# Servo_2016.net
KiCad netlist of a schematic drawn in EAGLE
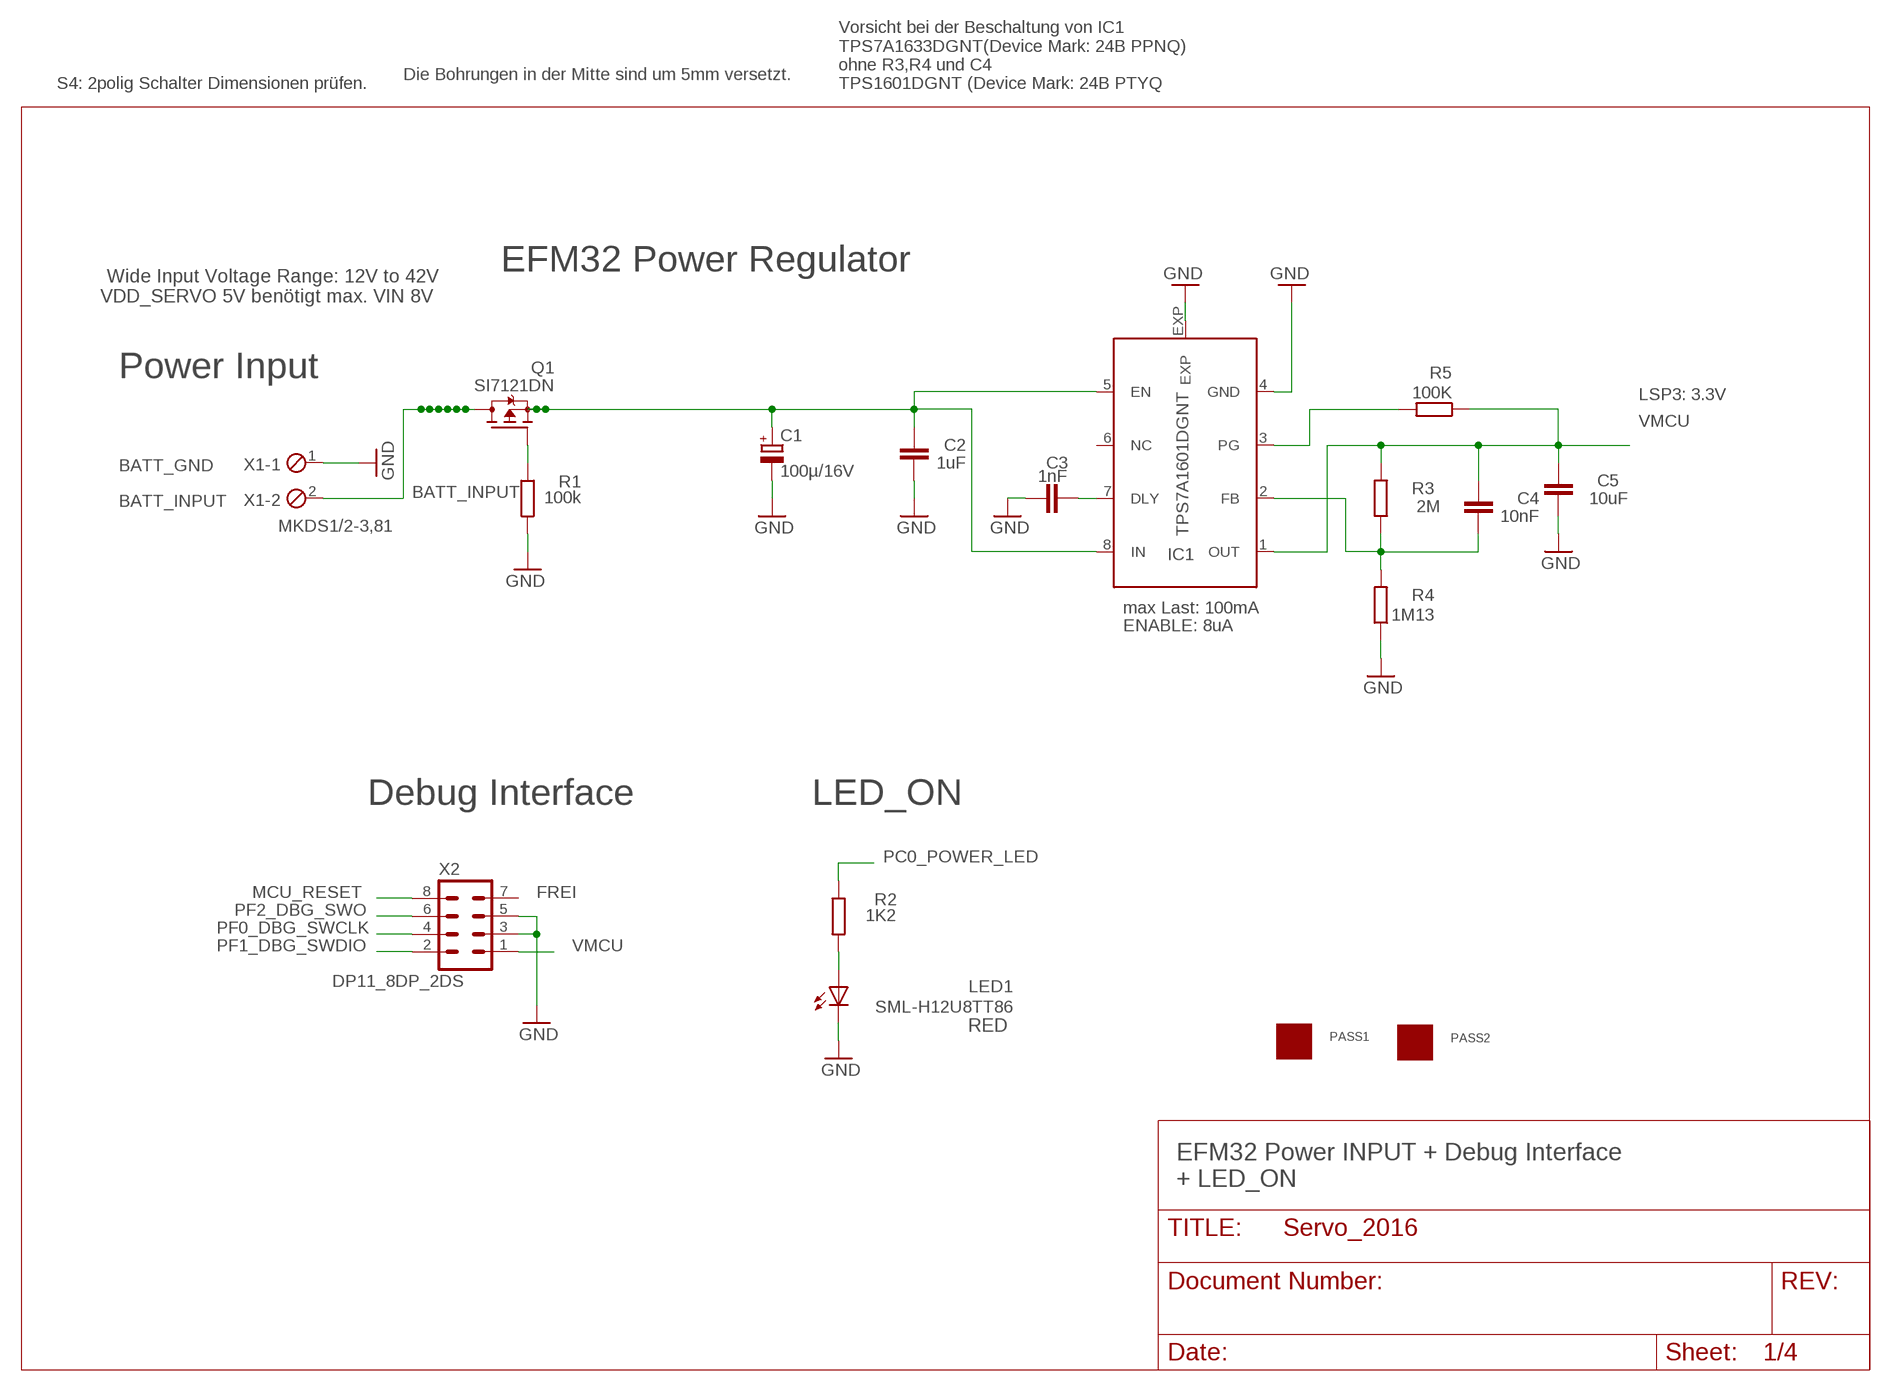
[diagram p0: schematic, sheet 1]
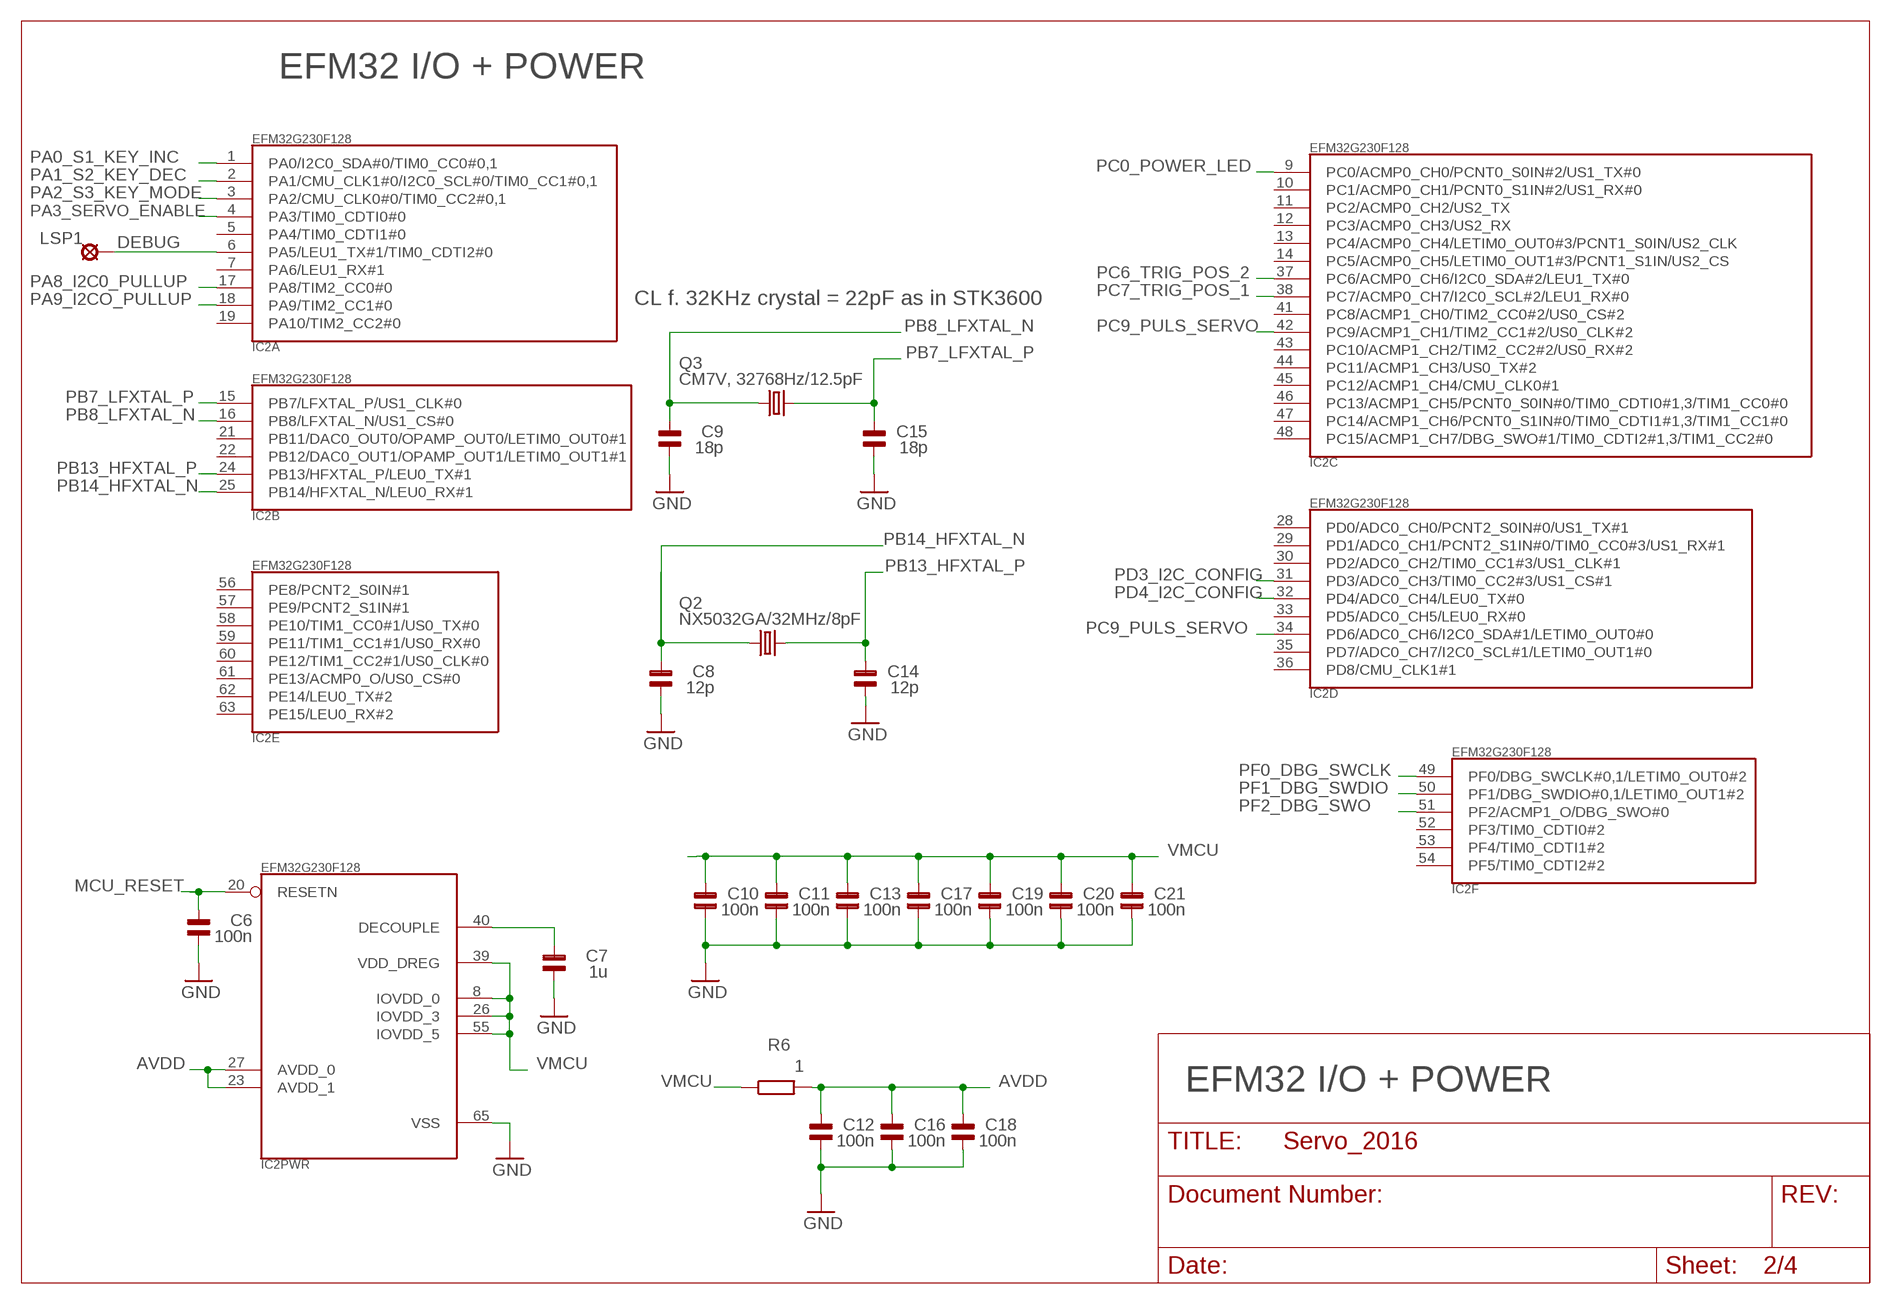
[diagram p1: schematic, sheet 2]
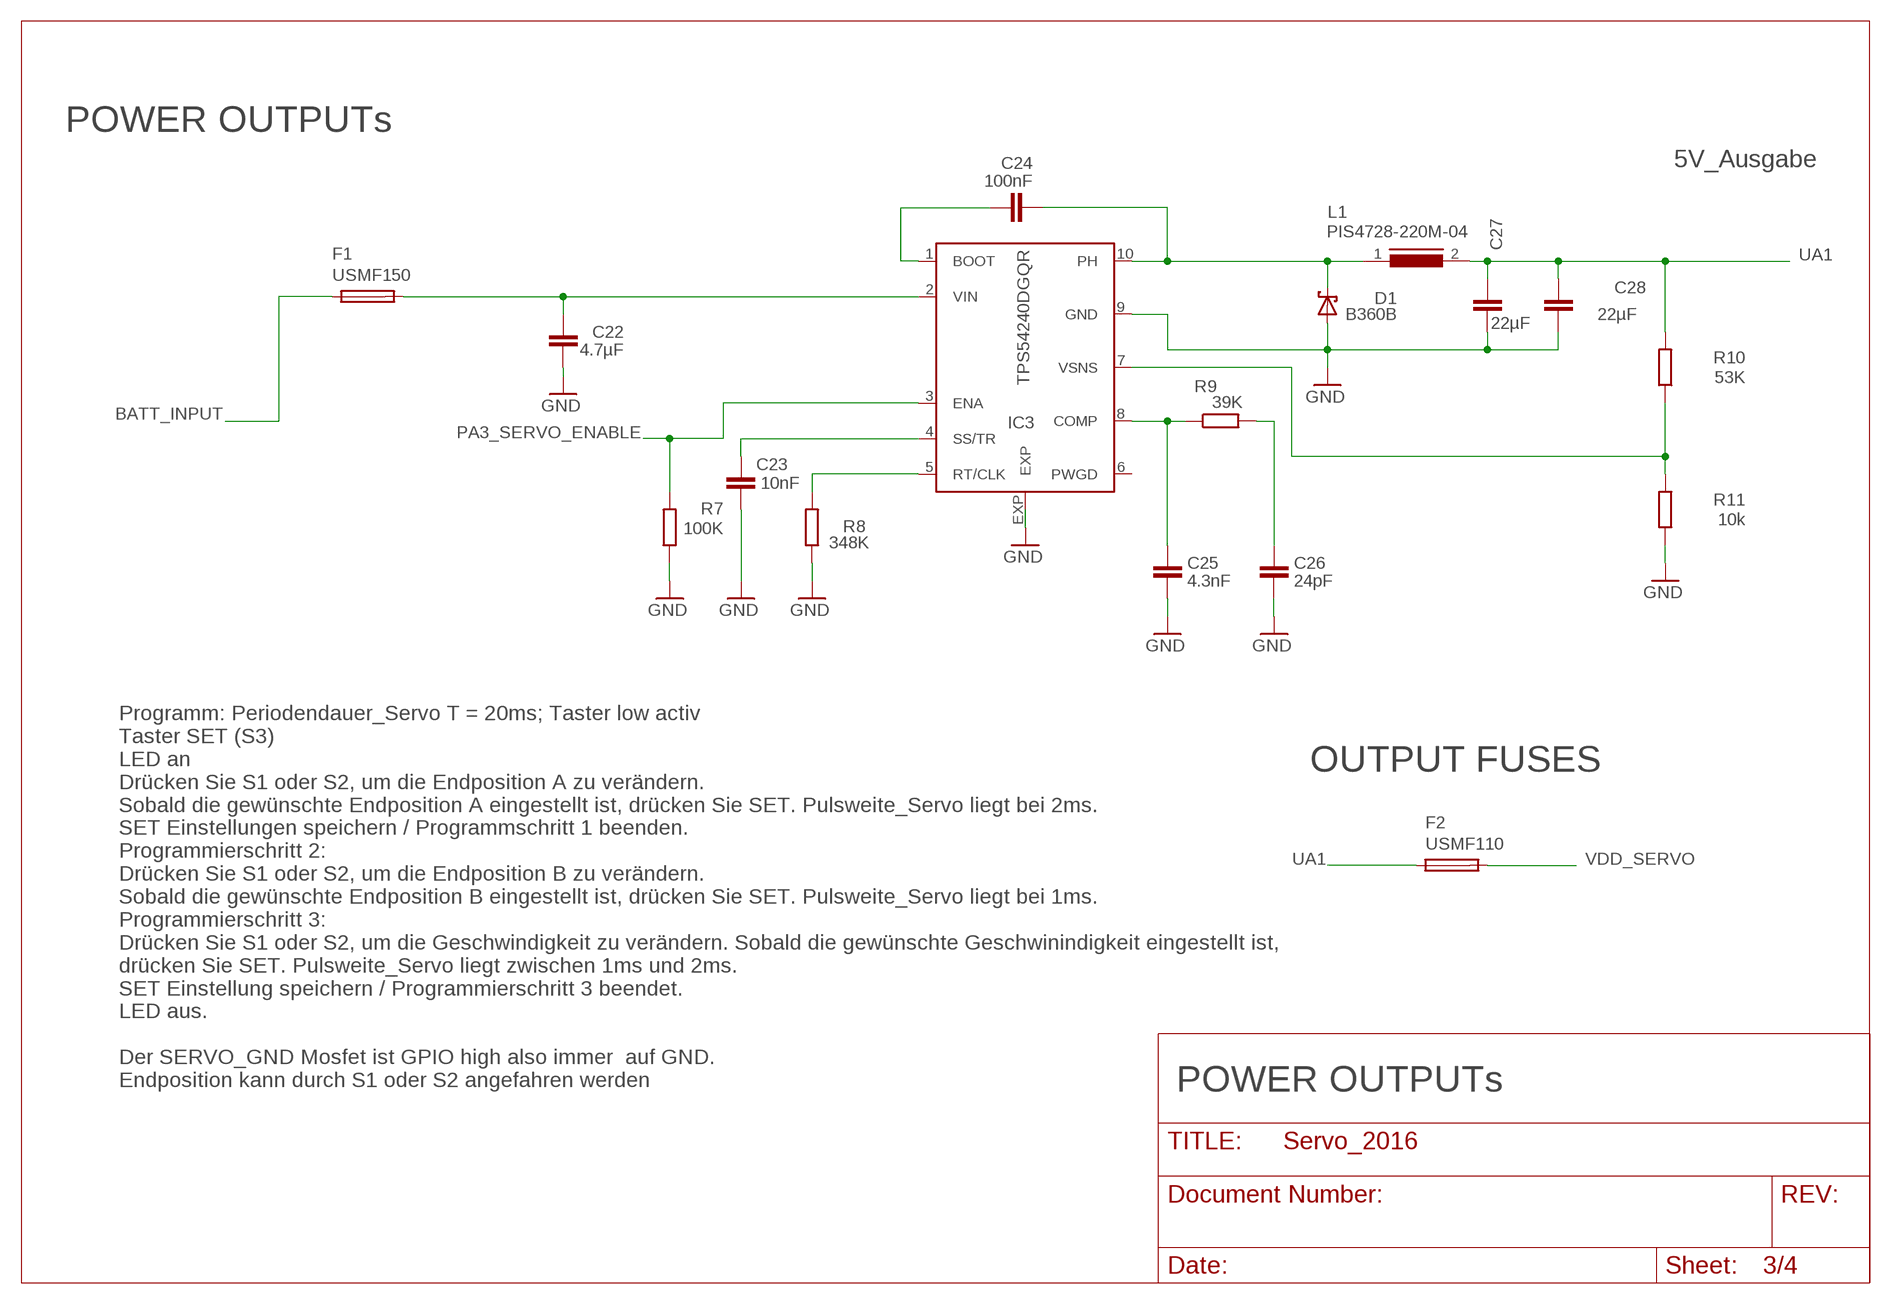
[diagram p2: schematic, sheet 3]
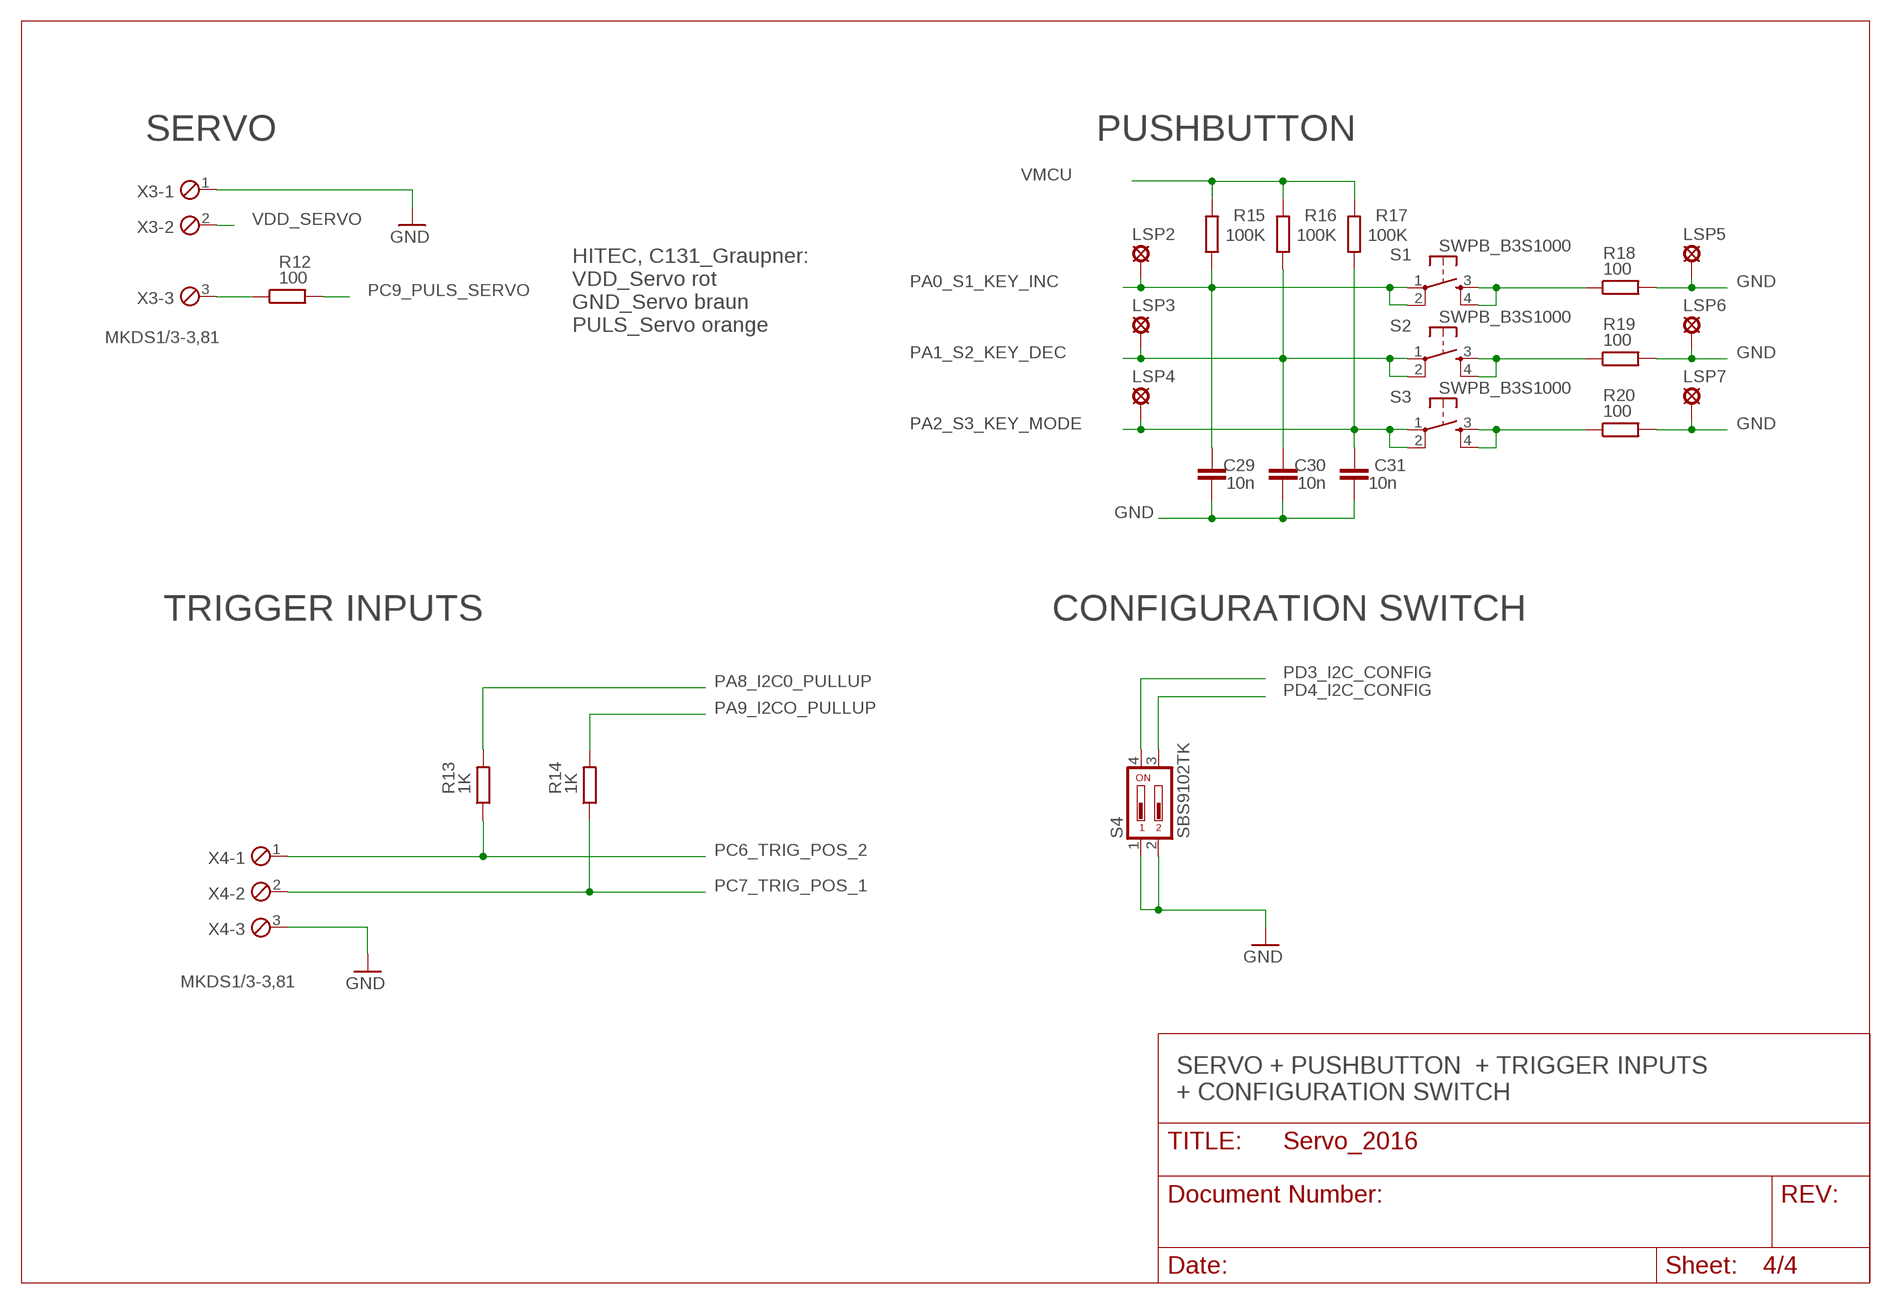
[diagram p3: schematic, sheet 4]

(export (version "E")
  (design (tool "Eeschema 10.0.6"))
  (components
    (comp (ref "C22")
      (value "4.7µF")
      (footprint "eagle-import:C1210")
      (libsource (lib "eagle-import") (part "C-EUC1210"))
    )
    (comp (ref "C23")
      (value "10nF")
      (footprint "eagle-import:C0603")
      (libsource (lib "eagle-import") (part "C-EUC0603"))
    )
    (comp (ref "C24")
      (value "100nF")
      (footprint "eagle-import:C0603")
      (libsource (lib "eagle-import") (part "C-EUC0603"))
    )
    (comp (ref "C25")
      (value "4.3nF")
      (footprint "eagle-import:C0603")
      (libsource (lib "eagle-import") (part "C-EUC0603"))
    )
    (comp (ref "C26")
      (value "24pF")
      (footprint "eagle-import:C0603")
      (libsource (lib "eagle-import") (part "C-EUC0603"))
    )
    (comp (ref "C27")
      (value "22µF")
      (footprint "eagle-import:C1210")
      (libsource (lib "eagle-import") (part "C-EUC1210"))
    )
    (comp (ref "C28")
      (value "22µF")
      (footprint "eagle-import:C1210")
      (libsource (lib "eagle-import") (part "C-EUC1210"))
    )
    (comp (ref "D1")
      (value "B360B")
      (footprint "eagle-import:SMB")
      (libsource (lib "eagle-import") (part "SCHOTTKY-DIODESMD"))
    )
    (comp (ref "F1")
      (value "USMF150")
      (footprint "eagle-import:PFUF_1210POLY")
      (libsource (lib "eagle-import") (part "PFUF"))
    )
    (comp (ref "F2")
      (value "USMF110")
      (footprint "eagle-import:PFUF_1210POLY")
      (libsource (lib "eagle-import") (part "PFUF"))
    )
    (comp (ref "IC3")
      (value "TPS54240DGQR")
      (footprint "eagle-import:S-PDSO-G10")
      (libsource (lib "eagle-import") (part "TPS54240DGQR"))
    )
    (comp (ref "L1")
      (value "PIS4728-220M-04")
      (footprint "eagle-import:DR127")
      (libsource (lib "eagle-import") (part "DR127"))
    )
    (comp (ref "R7")
      (value "100K")
      (footprint "eagle-import:R0805")
      (libsource (lib "eagle-import") (part "resistor_R-EU_R0805"))
    )
    (comp (ref "R8")
      (value "348K")
      (footprint "eagle-import:R0805")
      (libsource (lib "eagle-import") (part "resistor_R-EU_R0805"))
    )
    (comp (ref "R9")
      (value "39K")
      (footprint "eagle-import:R0805")
      (libsource (lib "eagle-import") (part "resistor_R-EU_R0805"))
    )
    (comp (ref "R10")
      (value "53K")
      (footprint "eagle-import:R0805")
      (libsource (lib "eagle-import") (part "resistor_R-EU_R0805"))
    )
    (comp (ref "R11")
      (value "10k")
      (footprint "eagle-import:R0805")
      (libsource (lib "eagle-import") (part "resistor_R-EU_R0805"))
    )
    (comp (ref "C1")
      (value "100µ/16V")
      (footprint "eagle-import:PANASONIC_E")
      (libsource (lib "eagle-import") (part "CPOL-EUE"))
    )
    (comp (ref "C2")
      (value "1uF")
      (footprint "eagle-import:C0603")
      (libsource (lib "eagle-import") (part "resistor_C-EUC0603"))
    )
    (comp (ref "C3")
      (value "1nF")
      (footprint "eagle-import:C0603")
      (libsource (lib "eagle-import") (part "resistor_C-EUC0603"))
    )
    (comp (ref "C4")
      (value "10nF")
      (footprint "eagle-import:C0603")
      (libsource (lib "eagle-import") (part "resistor_C-EUC0603"))
    )
    (comp (ref "C5")
      (value "10uF")
      (footprint "eagle-import:C1206")
      (libsource (lib "eagle-import") (part "resistor_C-EUC1206"))
    )
    (comp (ref "IC1")
      (value "TPS7A1601DGNT")
      (footprint "eagle-import:DGN_S-PDSO-G8-EXP")
      (libsource (lib "eagle-import") (part "TPS7A16"))
    )
    (comp (ref "LED1")
      (value "SML-H12U8TT86")
      (footprint "eagle-import:CHIPLED_0805")
      (libsource (lib "eagle-import") (part "LEDCHIPLED_0805"))
    )
    (comp (ref "PASS1")
      (value "ROUND_1MM1.5")
      (footprint "eagle-import:ROUND2_1.5MM")
      (libsource (lib "eagle-import") (part "ROUND_1MM1.5"))
    )
    (comp (ref "PASS2")
      (value "ROUND_1MM1.5")
      (footprint "eagle-import:ROUND2_1.5MM")
      (libsource (lib "eagle-import") (part "ROUND_1MM1.5"))
    )
    (comp (ref "Q1")
      (value "SI7121DN")
      (footprint "eagle-import:TRANSISTOR-FET_1212-8S")
      (libsource (lib "eagle-import") (part "TRANSISTOR-FET_SI7113DN"))
    )
    (comp (ref "R1")
      (value "100k")
      (footprint "eagle-import:R0805")
      (libsource (lib "eagle-import") (part "resistor_R-EU_R0805"))
    )
    (comp (ref "R2")
      (value "1K2")
      (footprint "eagle-import:R0805")
      (libsource (lib "eagle-import") (part "resistor_R-EU_R0805"))
    )
    (comp (ref "R3")
      (value "2M")
      (footprint "eagle-import:R0805")
      (libsource (lib "eagle-import") (part "resistor_R-EU_R0805"))
    )
    (comp (ref "R4")
      (value "1M13")
      (footprint "eagle-import:R0805")
      (libsource (lib "eagle-import") (part "resistor_R-EU_R0805"))
    )
    (comp (ref "R5")
      (value "100K")
      (footprint "eagle-import:R0805")
      (libsource (lib "eagle-import") (part "resistor_R-EU_R0805"))
    )
    (comp (ref "X1")
      (value "MKDS1/2-3,81")
      (footprint "eagle-import:2POL381")
      (libsource (lib "eagle-import") (part "MKDS1/2-3,81"))
    )
    (comp (ref "X2")
      (value "DP11_8DP_2DS")
      (footprint "eagle-import:DP11_8DP-2DS")
      (libsource (lib "eagle-import") (part "DP11_8DP_2DS"))
    )
    (comp (ref "C29")
      (value "10n")
      (footprint "eagle-import:C0603")
      (libsource (lib "eagle-import") (part "resistor_C-EUC0603"))
    )
    (comp (ref "C30")
      (value "10n")
      (footprint "eagle-import:C0603")
      (libsource (lib "eagle-import") (part "resistor_C-EUC0603"))
    )
    (comp (ref "C31")
      (value "10n")
      (footprint "eagle-import:C0603")
      (libsource (lib "eagle-import") (part "resistor_C-EUC0603"))
    )
    (comp (ref "LSP2")
      (value "(n.b.)LSP10")
      (footprint "eagle-import:LSP10")
      (libsource (lib "eagle-import") (part "LSP10"))
    )
    (comp (ref "LSP3")
      (value "(n.b.)LSP10")
      (footprint "eagle-import:LSP10")
      (libsource (lib "eagle-import") (part "LSP10"))
    )
    (comp (ref "LSP4")
      (value "(n.b.)LSP10")
      (footprint "eagle-import:LSP10")
      (libsource (lib "eagle-import") (part "LSP10"))
    )
    (comp (ref "LSP5")
      (value "(n.b.)LSP10")
      (footprint "eagle-import:LSP10")
      (libsource (lib "eagle-import") (part "LSP10"))
    )
    (comp (ref "LSP6")
      (value "(n.b.)LSP10")
      (footprint "eagle-import:LSP10")
      (libsource (lib "eagle-import") (part "LSP10"))
    )
    (comp (ref "LSP7")
      (value "(n.b.)LSP10")
      (footprint "eagle-import:LSP10")
      (libsource (lib "eagle-import") (part "LSP10"))
    )
    (comp (ref "R12")
      (value "100")
      (footprint "eagle-import:R0805")
      (libsource (lib "eagle-import") (part "resistor_R-EU_R0805"))
    )
    (comp (ref "R13")
      (value "1K")
      (footprint "eagle-import:R0805")
      (libsource (lib "eagle-import") (part "resistor_R-EU_R0805"))
    )
    (comp (ref "R14")
      (value "1K")
      (footprint "eagle-import:R0805")
      (libsource (lib "eagle-import") (part "resistor_R-EU_R0805"))
    )
    (comp (ref "R15")
      (value "100K")
      (footprint "eagle-import:R0805")
      (libsource (lib "eagle-import") (part "resistor_R-EU_R0805"))
    )
    (comp (ref "R16")
      (value "100K")
      (footprint "eagle-import:R0805")
      (libsource (lib "eagle-import") (part "resistor_R-EU_R0805"))
    )
    (comp (ref "R17")
      (value "100K")
      (footprint "eagle-import:R0805")
      (libsource (lib "eagle-import") (part "resistor_R-EU_R0805"))
    )
    (comp (ref "R18")
      (value "100")
      (footprint "eagle-import:R0805")
      (libsource (lib "eagle-import") (part "resistor_R-EU_R0805"))
    )
    (comp (ref "R19")
      (value "100")
      (footprint "eagle-import:R0805")
      (libsource (lib "eagle-import") (part "resistor_R-EU_R0805"))
    )
    (comp (ref "R20")
      (value "100")
      (footprint "eagle-import:R0805")
      (libsource (lib "eagle-import") (part "resistor_R-EU_R0805"))
    )
    (comp (ref "S1")
      (value "SWPB_B3S1000")
      (footprint "eagle-import:DTSM-6")
      (libsource (lib "eagle-import") (part "DTSM-6"))
    )
    (comp (ref "S2")
      (value "SWPB_B3S1000")
      (footprint "eagle-import:DTSM-6")
      (libsource (lib "eagle-import") (part "DTSM-6"))
    )
    (comp (ref "S3")
      (value "SWPB_B3S1000")
      (footprint "eagle-import:DTSM-6")
      (libsource (lib "eagle-import") (part "DTSM-6"))
    )
    (comp (ref "S4")
      (value "SBS9102TK")
      (footprint "eagle-import:CTS-219-02")
      (libsource (lib "eagle-import") (part "219-02"))
    )
    (comp (ref "X3")
      (value "MKDS1/3-3,81")
      (footprint "eagle-import:3POL381")
      (libsource (lib "eagle-import") (part "MKDS1/3-3,81"))
    )
    (comp (ref "X4")
      (value "MKDS1/3-3,81")
      (footprint "eagle-import:3POL381")
      (libsource (lib "eagle-import") (part "MKDS1/3-3,81"))
    )
    (comp (ref "C6")
      (value "100n")
      (footprint "eagle-import:0805")
      (libsource (lib "eagle-import") (part "C_SMD0805"))
    )
    (comp (ref "C7")
      (value "1u")
      (footprint "eagle-import:0805")
      (libsource (lib "eagle-import") (part "C_SMD0805"))
    )
    (comp (ref "C8")
      (value "12p")
      (footprint "eagle-import:0805")
      (libsource (lib "eagle-import") (part "C_SMD0805"))
    )
    (comp (ref "C9")
      (value "18p")
      (footprint "eagle-import:0805")
      (libsource (lib "eagle-import") (part "C_SMD0805"))
    )
    (comp (ref "C10")
      (value "100n")
      (footprint "eagle-import:0805")
      (libsource (lib "eagle-import") (part "C_SMD0805"))
    )
    (comp (ref "C11")
      (value "100n")
      (footprint "eagle-import:0805")
      (libsource (lib "eagle-import") (part "C_SMD0805"))
    )
    (comp (ref "C12")
      (value "100n")
      (footprint "eagle-import:0805")
      (libsource (lib "eagle-import") (part "C_SMD0805"))
    )
    (comp (ref "C13")
      (value "100n")
      (footprint "eagle-import:0805")
      (libsource (lib "eagle-import") (part "C_SMD0805"))
    )
    (comp (ref "C14")
      (value "12p")
      (footprint "eagle-import:0805")
      (libsource (lib "eagle-import") (part "C_SMD0805"))
    )
    (comp (ref "C15")
      (value "18p")
      (footprint "eagle-import:0805")
      (libsource (lib "eagle-import") (part "C_SMD0805"))
    )
    (comp (ref "C16")
      (value "100n")
      (footprint "eagle-import:0805")
      (libsource (lib "eagle-import") (part "C_SMD0805"))
    )
    (comp (ref "C17")
      (value "100n")
      (footprint "eagle-import:0805")
      (libsource (lib "eagle-import") (part "C_SMD0805"))
    )
    (comp (ref "C18")
      (value "100n")
      (footprint "eagle-import:0805")
      (libsource (lib "eagle-import") (part "C_SMD0805"))
    )
    (comp (ref "C19")
      (value "100n")
      (footprint "eagle-import:0805")
      (libsource (lib "eagle-import") (part "C_SMD0805"))
    )
    (comp (ref "C20")
      (value "100n")
      (footprint "eagle-import:0805")
      (libsource (lib "eagle-import") (part "C_SMD0805"))
    )
    (comp (ref "C21")
      (value "100n")
      (footprint "eagle-import:0805")
      (libsource (lib "eagle-import") (part "C_SMD0805"))
    )
    (comp (ref "IC2")
      (value "EFM32G230F128")
      (footprint "eagle-import:QFN64")
      (libsource (lib "eagle-import") (part "EFM32G230F128"))
    )
    (comp (ref "LSP1")
      (value "(n.b.)LSP10")
      (footprint "eagle-import:LSP10")
      (libsource (lib "eagle-import") (part "LSP10"))
    )
    (comp (ref "Q2")
      (value "NX5032GA/32MHz/8pF")
      (footprint "eagle-import:CRYSTAL2P5.0X3.2")
      (libsource (lib "eagle-import") (part "CRYSTAL2P5.0X3.2"))
    )
    (comp (ref "Q3")
      (value "CM7V, 32768Hz/12.5pF")
      (footprint "eagle-import:CRYSTAL2P3.2X1.5")
      (libsource (lib "eagle-import") (part "CRYSTAL2P"))
    )
    (comp (ref "R6")
      (value "1")
      (footprint "eagle-import:R0805")
      (libsource (lib "eagle-import") (part "R-EU_R0805"))
    )
  )
  (nets
    (net (code "1") (name "AVDD") (class "Default")
      (node (ref "C12") (pin "2") (pinfunction "2_2") (pintype "passive"))
      (node (ref "C16") (pin "2") (pinfunction "2_2") (pintype "passive"))
      (node (ref "C18") (pin "2") (pinfunction "2_2") (pintype "passive"))
      (node (ref "IC2") (pin "23") (pinfunction "AVDD_1_23") (pintype "power_in"))
      (node (ref "IC2") (pin "27") (pinfunction "AVDD_0_27") (pintype "power_in"))
      (node (ref "R6") (pin "2") (pinfunction "2_2") (pintype "passive"))
    )
    (net (code "2") (name "BATT_INPUT") (class "Default")
      (node (ref "F1") (pin "P$1") (pinfunction "1_P$1") (pintype "passive"))
      (node (ref "Q1") (pin "10") (pinfunction "D_10") (pintype "passive"))
      (node (ref "Q1") (pin "11") (pinfunction "D_11") (pintype "passive"))
      (node (ref "Q1") (pin "5") (pinfunction "D_5") (pintype "passive"))
      (node (ref "Q1") (pin "6") (pinfunction "D_6") (pintype "passive"))
      (node (ref "Q1") (pin "7") (pinfunction "D_7") (pintype "passive"))
      (node (ref "Q1") (pin "8") (pinfunction "D_8") (pintype "passive"))
      (node (ref "Q1") (pin "9") (pinfunction "D_9") (pintype "passive"))
      (node (ref "X1") (pin "2") (pinfunction "1_2") (pintype "passive"))
    )
    (net (code "3") (name "DEBUG") (class "Default")
      (node (ref "IC2") (pin "6") (pinfunction "PA5/LEU1_TX#1/TIM0_CDTI2#0_6") (pintype "bidirectional"))
      (node (ref "LSP1") (pin "MP") (pinfunction "MP_MP") (pintype "passive"))
    )
    (net (code "4") (name "GND") (class "Default")
      (node (ref "C1") (pin "-") (pinfunction "-_-") (pintype "passive"))
      (node (ref "C10") (pin "1") (pinfunction "1_1") (pintype "passive"))
      (node (ref "C11") (pin "1") (pinfunction "1_1") (pintype "passive"))
      (node (ref "C12") (pin "1") (pinfunction "1_1") (pintype "passive"))
      (node (ref "C13") (pin "1") (pinfunction "1_1") (pintype "passive"))
      (node (ref "C14") (pin "1") (pinfunction "1_1") (pintype "passive"))
      (node (ref "C15") (pin "1") (pinfunction "1_1") (pintype "passive"))
      (node (ref "C16") (pin "1") (pinfunction "1_1") (pintype "passive"))
      (node (ref "C17") (pin "1") (pinfunction "1_1") (pintype "passive"))
      (node (ref "C18") (pin "1") (pinfunction "1_1") (pintype "passive"))
      (node (ref "C19") (pin "1") (pinfunction "1_1") (pintype "passive"))
      (node (ref "C2") (pin "1") (pinfunction "1_1") (pintype "passive"))
      (node (ref "C20") (pin "1") (pinfunction "1_1") (pintype "passive"))
      (node (ref "C21") (pin "1") (pinfunction "1_1") (pintype "passive"))
      (node (ref "C22") (pin "2") (pinfunction "2_2") (pintype "passive"))
      (node (ref "C23") (pin "2") (pinfunction "2_2") (pintype "passive"))
      (node (ref "C25") (pin "2") (pinfunction "2_2") (pintype "passive"))
      (node (ref "C26") (pin "2") (pinfunction "2_2") (pintype "passive"))
      (node (ref "C27") (pin "2") (pinfunction "2_2") (pintype "passive"))
      (node (ref "C28") (pin "2") (pinfunction "2_2") (pintype "passive"))
      (node (ref "C29") (pin "1") (pinfunction "1_1") (pintype "passive"))
      (node (ref "C3") (pin "1") (pinfunction "1_1") (pintype "passive"))
      (node (ref "C30") (pin "1") (pinfunction "1_1") (pintype "passive"))
      (node (ref "C31") (pin "1") (pinfunction "1_1") (pintype "passive"))
      (node (ref "C5") (pin "1") (pinfunction "1_1") (pintype "passive"))
      (node (ref "C6") (pin "1") (pinfunction "1_1") (pintype "passive"))
      (node (ref "C7") (pin "1") (pinfunction "1_1") (pintype "passive"))
      (node (ref "C8") (pin "1") (pinfunction "1_1") (pintype "passive"))
      (node (ref "C9") (pin "1") (pinfunction "1_1") (pintype "passive"))
      (node (ref "D1") (pin "A") (pinfunction "A_A") (pintype "passive"))
      (node (ref "IC1") (pin "4") (pinfunction "GND_4") (pintype "passive"))
      (node (ref "IC1") (pin "EXP") (pinfunction "EXP_EXP") (pintype "passive"))
      (node (ref "IC2") (pin "65") (pinfunction "VSS_65") (pintype "power_in"))
      (node (ref "IC3") (pin "9") (pinfunction "GND_9") (pintype "power_in"))
      (node (ref "IC3") (pin "EXP") (pinfunction "EXP_EXP") (pintype "power_in"))
      (node (ref "LED1") (pin "C") (pinfunction "C_C") (pintype "passive"))
      (node (ref "LSP5") (pin "MP") (pinfunction "MP_MP") (pintype "passive"))
      (node (ref "LSP6") (pin "MP") (pinfunction "MP_MP") (pintype "passive"))
      (node (ref "LSP7") (pin "MP") (pinfunction "MP_MP") (pintype "passive"))
      (node (ref "R1") (pin "1") (pinfunction "1_1") (pintype "passive"))
      (node (ref "R11") (pin "1") (pinfunction "1_1") (pintype "passive"))
      (node (ref "R18") (pin "2") (pinfunction "2_2") (pintype "passive"))
      (node (ref "R19") (pin "2") (pinfunction "2_2") (pintype "passive"))
      (node (ref "R20") (pin "2") (pinfunction "2_2") (pintype "passive"))
      (node (ref "R4") (pin "1") (pinfunction "1_1") (pintype "passive"))
      (node (ref "R7") (pin "1") (pinfunction "1_1") (pintype "passive"))
      (node (ref "R8") (pin "1") (pinfunction "1_1") (pintype "passive"))
      (node (ref "S4") (pin "1") (pinfunction "1_1") (pintype "passive"))
      (node (ref "S4") (pin "2") (pinfunction "2_2") (pintype "passive"))
      (node (ref "X1") (pin "1") (pinfunction "1_1") (pintype "passive"))
      (node (ref "X2") (pin "3") (pinfunction "3_3") (pintype "passive"))
      (node (ref "X2") (pin "5") (pinfunction "5_5") (pintype "passive"))
      (node (ref "X3") (pin "1") (pinfunction "1_1") (pintype "passive"))
      (node (ref "X4") (pin "3") (pinfunction "1_3") (pintype "passive"))
    )
    (net (code "5") (name "MCU_RESET") (class "Default")
      (node (ref "C6") (pin "2") (pinfunction "2_2") (pintype "passive"))
      (node (ref "IC2") (pin "20") (pinfunction "RESETN_20") (pintype "passive"))
      (node (ref "X2") (pin "8") (pinfunction "8_8") (pintype "passive"))
    )
    (net (code "6") (name "Net-(C26-Pad1)") (class "Default")
      (node (ref "C26") (pin "1") (pinfunction "1_1") (pintype "passive"))
      (node (ref "R9") (pin "2") (pinfunction "2_2") (pintype "passive"))
    )
    (net (code "7") (name "Net-(F1-2)") (class "Default")
      (node (ref "C22") (pin "1") (pinfunction "1_1") (pintype "passive"))
      (node (ref "F1") (pin "P$2") (pinfunction "2_P$2") (pintype "passive"))
      (node (ref "IC3") (pin "2") (pinfunction "VIN_2") (pintype "input"))
    )
    (net (code "8") (name "Net-(IC1-DLY)") (class "Default")
      (node (ref "C3") (pin "2") (pinfunction "2_2") (pintype "passive"))
      (node (ref "IC1") (pin "7") (pinfunction "DLY_7") (pintype "output"))
    )
    (net (code "9") (name "Net-(IC1-EN)") (class "Default")
      (node (ref "C1") (pin "+") (pinfunction "+_+") (pintype "passive"))
      (node (ref "C2") (pin "2") (pinfunction "2_2") (pintype "passive"))
      (node (ref "IC1") (pin "5") (pinfunction "EN_5") (pintype "input"))
      (node (ref "IC1") (pin "8") (pinfunction "IN_8") (pintype "passive"))
      (node (ref "Q1") (pin "1") (pinfunction "S_1") (pintype "passive"))
      (node (ref "Q1") (pin "2") (pinfunction "S_2") (pintype "passive"))
      (node (ref "Q1") (pin "3") (pinfunction "S_3") (pintype "passive"))
    )
    (net (code "10") (name "Net-(IC1-FB)") (class "Default")
      (node (ref "C4") (pin "1") (pinfunction "1_1") (pintype "passive"))
      (node (ref "IC1") (pin "2") (pinfunction "FB_2") (pintype "input"))
      (node (ref "R3") (pin "1") (pinfunction "1_1") (pintype "passive"))
      (node (ref "R4") (pin "2") (pinfunction "2_2") (pintype "passive"))
    )
    (net (code "11") (name "Net-(IC1-PG)") (class "Default")
      (node (ref "IC1") (pin "3") (pinfunction "PG_3") (pintype "output"))
      (node (ref "R5") (pin "2") (pinfunction "2_2") (pintype "passive"))
    )
    (net (code "12") (name "Net-(IC2G-DECOUPLE)") (class "Default")
      (node (ref "C7") (pin "2") (pinfunction "2_2") (pintype "passive"))
      (node (ref "IC2") (pin "40") (pinfunction "DECOUPLE_40") (pintype "power_in"))
    )
    (net (code "13") (name "Net-(IC3-BOOT)") (class "Default")
      (node (ref "C24") (pin "2") (pinfunction "2_2") (pintype "passive"))
      (node (ref "IC3") (pin "1") (pinfunction "BOOT_1") (pintype "output"))
    )
    (net (code "14") (name "Net-(IC3-COMP)") (class "Default")
      (node (ref "C25") (pin "1") (pinfunction "1_1") (pintype "passive"))
      (node (ref "IC3") (pin "8") (pinfunction "COMP_8") (pintype "input"))
      (node (ref "R9") (pin "1") (pinfunction "1_1") (pintype "passive"))
    )
    (net (code "15") (name "Net-(IC3-PH)") (class "Default")
      (node (ref "C24") (pin "1") (pinfunction "1_1") (pintype "passive"))
      (node (ref "D1") (pin "C") (pinfunction "C_C") (pintype "passive"))
      (node (ref "IC3") (pin "10") (pinfunction "PH_10") (pintype "output"))
      (node (ref "L1") (pin "1") (pinfunction "1_1") (pintype "passive"))
    )
    (net (code "16") (name "Net-(IC3-RT{slash}CLK)") (class "Default")
      (node (ref "IC3") (pin "5") (pinfunction "RT/CLK_5") (pintype "input"))
      (node (ref "R8") (pin "2") (pinfunction "2_2") (pintype "passive"))
    )
    (net (code "17") (name "Net-(IC3-SS{slash}TR)") (class "Default")
      (node (ref "C23") (pin "1") (pinfunction "1_1") (pintype "passive"))
      (node (ref "IC3") (pin "4") (pinfunction "SS/TR_4") (pintype "input"))
    )
    (net (code "18") (name "Net-(IC3-VSNS)") (class "Default")
      (node (ref "IC3") (pin "7") (pinfunction "VSNS_7") (pintype "input"))
      (node (ref "R10") (pin "1") (pinfunction "1_1") (pintype "passive"))
      (node (ref "R11") (pin "2") (pinfunction "2_2") (pintype "passive"))
    )
    (net (code "19") (name "Net-(LED1-PadA)") (class "Default")
      (node (ref "LED1") (pin "A") (pinfunction "A_A") (pintype "passive"))
      (node (ref "R2") (pin "2") (pinfunction "2_2") (pintype "passive"))
    )
    (net (code "20") (name "Net-(Q1-G)") (class "Default")
      (node (ref "Q1") (pin "4") (pinfunction "G_4") (pintype "passive"))
      (node (ref "R1") (pin "2") (pinfunction "2_2") (pintype "passive"))
    )
    (net (code "21") (name "Net-(R18-Pad1)") (class "Default")
      (node (ref "R18") (pin "1") (pinfunction "1_1") (pintype "passive"))
      (node (ref "S1") (pin "3") (pinfunction "3_3") (pintype "passive"))
      (node (ref "S1") (pin "4") (pinfunction "4_4") (pintype "passive"))
    )
    (net (code "22") (name "Net-(R19-Pad1)") (class "Default")
      (node (ref "R19") (pin "1") (pinfunction "1_1") (pintype "passive"))
      (node (ref "S2") (pin "3") (pinfunction "3_3") (pintype "passive"))
      (node (ref "S2") (pin "4") (pinfunction "4_4") (pintype "passive"))
    )
    (net (code "23") (name "Net-(R20-Pad1)") (class "Default")
      (node (ref "R20") (pin "1") (pinfunction "1_1") (pintype "passive"))
      (node (ref "S3") (pin "3") (pinfunction "3_3") (pintype "passive"))
      (node (ref "S3") (pin "4") (pinfunction "4_4") (pintype "passive"))
    )
    (net (code "24") (name "Net-(X3C-1)") (class "Default")
      (node (ref "R12") (pin "1") (pinfunction "1_1") (pintype "passive"))
      (node (ref "X3") (pin "3") (pinfunction "1_3") (pintype "passive"))
    )
    (net (code "25") (name "PA0_S1_KEY_INC") (class "Default")
      (node (ref "C29") (pin "2") (pinfunction "2_2") (pintype "passive"))
      (node (ref "IC2") (pin "1") (pinfunction "PA0/I2C0_SDA#0/TIM0_CC0#0,1_1") (pintype "bidirectional"))
      (node (ref "LSP2") (pin "MP") (pinfunction "MP_MP") (pintype "passive"))
      (node (ref "R15") (pin "1") (pinfunction "1_1") (pintype "passive"))
      (node (ref "S1") (pin "1") (pinfunction "1_1") (pintype "passive"))
      (node (ref "S1") (pin "2") (pinfunction "2_2") (pintype "passive"))
    )
    (net (code "26") (name "PA1_S2_KEY_DEC") (class "Default")
      (node (ref "C30") (pin "2") (pinfunction "2_2") (pintype "passive"))
      (node (ref "IC2") (pin "2") (pinfunction "PA1/CMU_CLK1#0/I2C0_SCL#0/TIM0_CC1#0,1_2") (pintype "bidirectional"))
      (node (ref "LSP3") (pin "MP") (pinfunction "MP_MP") (pintype "passive"))
      (node (ref "R16") (pin "1") (pinfunction "1_1") (pintype "passive"))
      (node (ref "S2") (pin "1") (pinfunction "1_1") (pintype "passive"))
      (node (ref "S2") (pin "2") (pinfunction "2_2") (pintype "passive"))
    )
    (net (code "27") (name "PA2_S3_KEY_MODE") (class "Default")
      (node (ref "C31") (pin "2") (pinfunction "2_2") (pintype "passive"))
      (node (ref "IC2") (pin "3") (pinfunction "PA2/CMU_CLK0#0/TIM0_CC2#0,1_3") (pintype "bidirectional"))
      (node (ref "LSP4") (pin "MP") (pinfunction "MP_MP") (pintype "passive"))
      (node (ref "R17") (pin "1") (pinfunction "1_1") (pintype "passive"))
      (node (ref "S3") (pin "1") (pinfunction "1_1") (pintype "passive"))
      (node (ref "S3") (pin "2") (pinfunction "2_2") (pintype "passive"))
    )
    (net (code "28") (name "PA3_SERVO_ENABLE") (class "Default")
      (node (ref "IC2") (pin "4") (pinfunction "PA3/TIM0_CDTI0#0_4") (pintype "bidirectional"))
      (node (ref "IC3") (pin "3") (pinfunction "ENA_3") (pintype "input"))
      (node (ref "R7") (pin "2") (pinfunction "2_2") (pintype "passive"))
    )
    (net (code "29") (name "PA8_I2C0_PULLUP") (class "Default")
      (node (ref "IC2") (pin "17") (pinfunction "PA8/TIM2_CC0#0_17") (pintype "bidirectional"))
      (node (ref "R13") (pin "2") (pinfunction "2_2") (pintype "passive"))
    )
    (net (code "30") (name "PA9_I2CO_PULLUP") (class "Default")
      (node (ref "IC2") (pin "18") (pinfunction "PA9/TIM2_CC1#0_18") (pintype "bidirectional"))
      (node (ref "R14") (pin "2") (pinfunction "2_2") (pintype "passive"))
    )
    (net (code "31") (name "PB7_LFXTAL_P") (class "Default")
      (node (ref "C15") (pin "2") (pinfunction "2_2") (pintype "passive"))
      (node (ref "IC2") (pin "15") (pinfunction "PB7/LFXTAL_P/US1_CLK#0_15") (pintype "bidirectional"))
      (node (ref "Q3") (pin "2") (pinfunction "2_2") (pintype "passive"))
    )
    (net (code "32") (name "PB8_LFXTAL_N") (class "Default")
      (node (ref "C9") (pin "2") (pinfunction "2_2") (pintype "passive"))
      (node (ref "IC2") (pin "16") (pinfunction "PB8/LFXTAL_N/US1_CS#0_16") (pintype "bidirectional"))
      (node (ref "Q3") (pin "1") (pinfunction "1_1") (pintype "passive"))
    )
    (net (code "33") (name "PB13_HFXTAL_P") (class "Default")
      (node (ref "C14") (pin "2") (pinfunction "2_2") (pintype "passive"))
      (node (ref "IC2") (pin "24") (pinfunction "PB13/HFXTAL_P/LEU0_TX#1_24") (pintype "bidirectional"))
      (node (ref "Q2") (pin "2") (pinfunction "2_2") (pintype "passive"))
    )
    (net (code "34") (name "PB14_HFXTAL_N") (class "Default")
      (node (ref "C8") (pin "2") (pinfunction "2_2") (pintype "passive"))
      (node (ref "IC2") (pin "25") (pinfunction "PB14/HFXTAL_N/LEU0_RX#1_25") (pintype "bidirectional"))
      (node (ref "Q2") (pin "1") (pinfunction "1_1") (pintype "passive"))
    )
    (net (code "35") (name "PC0_POWER_LED") (class "Default")
      (node (ref "IC2") (pin "9") (pinfunction "PC0/ACMP0_CH0/PCNT0_S0IN#2/US1_TX#0_9") (pintype "bidirectional"))
      (node (ref "R2") (pin "1") (pinfunction "1_1") (pintype "passive"))
    )
    (net (code "36") (name "PC6_TRIG_POS_2") (class "Default")
      (node (ref "IC2") (pin "37") (pinfunction "PC6/ACMP0_CH6/I2C0_SDA#2/LEU1_TX#0_37") (pintype "bidirectional"))
      (node (ref "R13") (pin "1") (pinfunction "1_1") (pintype "passive"))
      (node (ref "X4") (pin "1") (pinfunction "1_1") (pintype "passive"))
    )
    (net (code "37") (name "PC7_TRIG_POS_1") (class "Default")
      (node (ref "IC2") (pin "38") (pinfunction "PC7/ACMP0_CH7/I2C0_SCL#2/LEU1_RX#0_38") (pintype "bidirectional"))
      (node (ref "R14") (pin "1") (pinfunction "1_1") (pintype "passive"))
      (node (ref "X4") (pin "2") (pinfunction "1_2") (pintype "passive"))
    )
    (net (code "38") (name "PC9_PULS_SERVO") (class "Default")
      (node (ref "IC2") (pin "34") (pinfunction "PD6/ADC0_CH6/I2C0_SDA#1/LETIM0_OUT0#0_34") (pintype "bidirectional"))
      (node (ref "IC2") (pin "42") (pinfunction "PC9/ACMP1_CH1/TIM2_CC1#2/US0_CLK#2_42") (pintype "bidirectional"))
      (node (ref "R12") (pin "2") (pinfunction "2_2") (pintype "passive"))
    )
    (net (code "39") (name "PD3_I2C_CONFIG") (class "Default")
      (node (ref "IC2") (pin "31") (pinfunction "PD3/ADC0_CH3/TIM0_CC2#3/US1_CS#1_31") (pintype "bidirectional"))
      (node (ref "S4") (pin "4") (pinfunction "4_4") (pintype "passive"))
    )
    (net (code "40") (name "PD4_I2C_CONFIG") (class "Default")
      (node (ref "IC2") (pin "32") (pinfunction "PD4/ADC0_CH4/LEU0_TX#0_32") (pintype "bidirectional"))
      (node (ref "S4") (pin "3") (pinfunction "3_3") (pintype "passive"))
    )
    (net (code "41") (name "PF0_DBG_SWCLK") (class "Default")
      (node (ref "IC2") (pin "49") (pinfunction "PF0/DBG_SWCLK#0,1/LETIM0_OUT0#2_49") (pintype "bidirectional"))
      (node (ref "X2") (pin "4") (pinfunction "4_4") (pintype "passive"))
    )
    (net (code "42") (name "PF1_DBG_SWDIO") (class "Default")
      (node (ref "IC2") (pin "50") (pinfunction "PF1/DBG_SWDIO#0,1/LETIM0_OUT1#2_50") (pintype "bidirectional"))
      (node (ref "X2") (pin "2") (pinfunction "2_2") (pintype "passive"))
    )
    (net (code "43") (name "PF2_DBG_SWO") (class "Default")
      (node (ref "IC2") (pin "51") (pinfunction "PF2/ACMP1_O/DBG_SWO#0_51") (pintype "bidirectional"))
      (node (ref "X2") (pin "6") (pinfunction "6_6") (pintype "passive"))
    )
    (net (code "44") (name "UA1") (class "Default")
      (node (ref "C27") (pin "1") (pinfunction "1_1") (pintype "passive"))
      (node (ref "C28") (pin "1") (pinfunction "1_1") (pintype "passive"))
      (node (ref "F2") (pin "P$1") (pinfunction "1_P$1") (pintype "passive"))
      (node (ref "L1") (pin "2") (pinfunction "2_2") (pintype "passive"))
      (node (ref "R10") (pin "2") (pinfunction "2_2") (pintype "passive"))
    )
    (net (code "45") (name "VDD_SERVO") (class "Default")
      (node (ref "F2") (pin "P$2") (pinfunction "2_P$2") (pintype "passive"))
      (node (ref "X3") (pin "2") (pinfunction "1_2") (pintype "passive"))
    )
    (net (code "46") (name "VMCU") (class "Default")
      (node (ref "C10") (pin "2") (pinfunction "2_2") (pintype "passive"))
      (node (ref "C11") (pin "2") (pinfunction "2_2") (pintype "passive"))
      (node (ref "C13") (pin "2") (pinfunction "2_2") (pintype "passive"))
      (node (ref "C17") (pin "2") (pinfunction "2_2") (pintype "passive"))
      (node (ref "C19") (pin "2") (pinfunction "2_2") (pintype "passive"))
      (node (ref "C20") (pin "2") (pinfunction "2_2") (pintype "passive"))
      (node (ref "C21") (pin "2") (pinfunction "2_2") (pintype "passive"))
      (node (ref "C4") (pin "2") (pinfunction "2_2") (pintype "passive"))
      (node (ref "C5") (pin "2") (pinfunction "2_2") (pintype "passive"))
      (node (ref "IC1") (pin "1") (pinfunction "OUT_1") (pintype "output"))
      (node (ref "IC2") (pin "26") (pinfunction "IOVDD_3_26") (pintype "power_in"))
      (node (ref "IC2") (pin "39") (pinfunction "VDD_DREG_39") (pintype "power_in"))
      (node (ref "IC2") (pin "55") (pinfunction "IOVDD_5_55") (pintype "power_in"))
      (node (ref "IC2") (pin "8") (pinfunction "IOVDD_0_8") (pintype "power_in"))
      (node (ref "R15") (pin "2") (pinfunction "2_2") (pintype "passive"))
      (node (ref "R16") (pin "2") (pinfunction "2_2") (pintype "passive"))
      (node (ref "R17") (pin "2") (pinfunction "2_2") (pintype "passive"))
      (node (ref "R3") (pin "2") (pinfunction "2_2") (pintype "passive"))
      (node (ref "R5") (pin "1") (pinfunction "1_1") (pintype "passive"))
      (node (ref "R6") (pin "1") (pinfunction "1_1") (pintype "passive"))
      (node (ref "X2") (pin "1") (pinfunction "1_1") (pintype "passive"))
    )
    (net (code "47") (name "unconnected-(IC1-NC-Pad6)") (class "Default")
      (node (ref "IC1") (pin "6") (pinfunction "NC_6") (pintype "no_connect"))
    )
    (net (code "48") (name "unconnected-(IC2A-PA4{slash}TIM0_CDTI1#0-Pad5)") (class "Default")
      (node (ref "IC2") (pin "5") (pinfunction "PA4/TIM0_CDTI1#0_5") (pintype "bidirectional"))
    )
    (net (code "49") (name "unconnected-(IC2A-PA6{slash}LEU1_RX#1-Pad7)") (class "Default")
      (node (ref "IC2") (pin "7") (pinfunction "PA6/LEU1_RX#1_7") (pintype "bidirectional"))
    )
    (net (code "50") (name "unconnected-(IC2A-PA10{slash}TIM2_CC2#0-Pad19)") (class "Default")
      (node (ref "IC2") (pin "19") (pinfunction "PA10/TIM2_CC2#0_19") (pintype "bidirectional"))
    )
    (net (code "51") (name "unconnected-(IC2B-PB11{slash}DAC0_OUT0{slash}OPAMP_OUT0{slash}LETIM0_OUT0#1-Pad21)") (class "Default")
      (node (ref "IC2") (pin "21") (pinfunction "PB11/DAC0_OUT0/OPAMP_OUT0/LETIM0_OUT0#1_21") (pintype "bidirectional"))
    )
    (net (code "52") (name "unconnected-(IC2B-PB12{slash}DAC0_OUT1{slash}OPAMP_OUT1{slash}LETIM0_OUT1#1-Pad22)") (class "Default")
      (node (ref "IC2") (pin "22") (pinfunction "PB12/DAC0_OUT1/OPAMP_OUT1/LETIM0_OUT1#1_22") (pintype "bidirectional"))
    )
    (net (code "53") (name "unconnected-(IC2C-PC1{slash}ACMP0_CH1{slash}PCNT0_S1IN#2{slash}US1_RX#0-Pad10)") (class "Default")
      (node (ref "IC2") (pin "10") (pinfunction "PC1/ACMP0_CH1/PCNT0_S1IN#2/US1_RX#0_10") (pintype "bidirectional"))
    )
    (net (code "54") (name "unconnected-(IC2C-PC2{slash}ACMP0_CH2{slash}US2_TX-Pad11)") (class "Default")
      (node (ref "IC2") (pin "11") (pinfunction "PC2/ACMP0_CH2/US2_TX_11") (pintype "bidirectional"))
    )
    (net (code "55") (name "unconnected-(IC2C-PC3{slash}ACMP0_CH3{slash}US2_RX-Pad12)") (class "Default")
      (node (ref "IC2") (pin "12") (pinfunction "PC3/ACMP0_CH3/US2_RX_12") (pintype "bidirectional"))
    )
    (net (code "56") (name "unconnected-(IC2C-PC4{slash}ACMP0_CH4{slash}LETIM0_OUT0#3{slash}PCNT1_S0IN{slash}US2_CLK-Pad13)") (class "Default")
      (node (ref "IC2") (pin "13") (pinfunction "PC4/ACMP0_CH4/LETIM0_OUT0#3/PCNT1_S0IN/US2_CLK_13") (pintype "bidirectional"))
    )
    (net (code "57") (name "unconnected-(IC2C-PC5{slash}ACMP0_CH5{slash}LETIM0_OUT1#3{slash}PCNT1_S1IN{slash}US2_CS-Pad14)") (class "Default")
      (node (ref "IC2") (pin "14") (pinfunction "PC5/ACMP0_CH5/LETIM0_OUT1#3/PCNT1_S1IN/US2_CS_14") (pintype "bidirectional"))
    )
    (net (code "58") (name "unconnected-(IC2C-PC8{slash}ACMP1_CH0{slash}TIM2_CC0#2{slash}US0_CS#2-Pad41)") (class "Default")
      (node (ref "IC2") (pin "41") (pinfunction "PC8/ACMP1_CH0/TIM2_CC0#2/US0_CS#2_41") (pintype "bidirectional"))
    )
    (net (code "59") (name "unconnected-(IC2C-PC10{slash}ACMP1_CH2{slash}TIM2_CC2#2{slash}US0_RX#2-Pad43)") (class "Default")
      (node (ref "IC2") (pin "43") (pinfunction "PC10/ACMP1_CH2/TIM2_CC2#2/US0_RX#2_43") (pintype "bidirectional"))
    )
    (net (code "60") (name "unconnected-(IC2C-PC11{slash}ACMP1_CH3{slash}US0_TX#2-Pad44)") (class "Default")
      (node (ref "IC2") (pin "44") (pinfunction "PC11/ACMP1_CH3/US0_TX#2_44") (pintype "bidirectional"))
    )
    (net (code "61") (name "unconnected-(IC2C-PC12{slash}ACMP1_CH4{slash}CMU_CLK0#1-Pad45)") (class "Default")
      (node (ref "IC2") (pin "45") (pinfunction "PC12/ACMP1_CH4/CMU_CLK0#1_45") (pintype "bidirectional"))
    )
    (net (code "62") (name "unconnected-(IC2C-PC13{slash}ACMP1_CH5{slash}PCNT0_S0IN#0{slash}TIM0_CDTI0#1,3{slash}TIM1_CC0#0-Pad46)") (class "Default")
      (node (ref "IC2") (pin "46") (pinfunction "PC13/ACMP1_CH5/PCNT0_S0IN#0/TIM0_CDTI0#1,3/TIM1_CC0#0_46") (pintype "bidirectional"))
    )
    (net (code "63") (name "unconnected-(IC2C-PC14{slash}ACMP1_CH6{slash}PCNT0_S1IN#0{slash}TIM0_CDTI1#1,3{slash}TIM1_CC1#0-Pad47)") (class "Default")
      (node (ref "IC2") (pin "47") (pinfunction "PC14/ACMP1_CH6/PCNT0_S1IN#0/TIM0_CDTI1#1,3/TIM1_CC1#0_47") (pintype "bidirectional"))
    )
    (net (code "64") (name "unconnected-(IC2C-PC15{slash}ACMP1_CH7{slash}DBG_SWO#1{slash}TIM0_CDTI2#1,3{slash}TIM1_CC2#0-Pad48)") (class "Default")
      (node (ref "IC2") (pin "48") (pinfunction "PC15/ACMP1_CH7/DBG_SWO#1/TIM0_CDTI2#1,3/TIM1_CC2#0_48") (pintype "bidirectional"))
    )
    (net (code "65") (name "unconnected-(IC2D-PD0{slash}ADC0_CH0{slash}PCNT2_S0IN#0{slash}US1_TX#1-Pad28)") (class "Default")
      (node (ref "IC2") (pin "28") (pinfunction "PD0/ADC0_CH0/PCNT2_S0IN#0/US1_TX#1_28") (pintype "bidirectional"))
    )
    (net (code "66") (name "unconnected-(IC2D-PD1{slash}ADC0_CH1{slash}PCNT2_S1IN#0{slash}TIM0_CC0#3{slash}US1_RX#1-Pad29)") (class "Default")
      (node (ref "IC2") (pin "29") (pinfunction "PD1/ADC0_CH1/PCNT2_S1IN#0/TIM0_CC0#3/US1_RX#1_29") (pintype "bidirectional"))
    )
    (net (code "67") (name "unconnected-(IC2D-PD2{slash}ADC0_CH2{slash}TIM0_CC1#3{slash}US1_CLK#1-Pad30)") (class "Default")
      (node (ref "IC2") (pin "30") (pinfunction "PD2/ADC0_CH2/TIM0_CC1#3/US1_CLK#1_30") (pintype "bidirectional"))
    )
    (net (code "68") (name "unconnected-(IC2D-PD5{slash}ADC0_CH5{slash}LEU0_RX#0-Pad33)") (class "Default")
      (node (ref "IC2") (pin "33") (pinfunction "PD5/ADC0_CH5/LEU0_RX#0_33") (pintype "bidirectional"))
    )
    (net (code "69") (name "unconnected-(IC2D-PD7{slash}ADC0_CH7{slash}I2C0_SCL#1{slash}LETIM0_OUT1#0-Pad35)") (class "Default")
      (node (ref "IC2") (pin "35") (pinfunction "PD7/ADC0_CH7/I2C0_SCL#1/LETIM0_OUT1#0_35") (pintype "bidirectional"))
    )
    (net (code "70") (name "unconnected-(IC2D-PD8{slash}CMU_CLK1#1-Pad36)") (class "Default")
      (node (ref "IC2") (pin "36") (pinfunction "PD8/CMU_CLK1#1_36") (pintype "bidirectional"))
    )
    (net (code "71") (name "unconnected-(IC2E-PE8{slash}PCNT2_S0IN#1-Pad56)") (class "Default")
      (node (ref "IC2") (pin "56") (pinfunction "PE8/PCNT2_S0IN#1_56") (pintype "bidirectional"))
    )
    (net (code "72") (name "unconnected-(IC2E-PE9{slash}PCNT2_S1IN#1-Pad57)") (class "Default")
      (node (ref "IC2") (pin "57") (pinfunction "PE9/PCNT2_S1IN#1_57") (pintype "bidirectional"))
    )
    (net (code "73") (name "unconnected-(IC2E-PE10{slash}TIM1_CC0#1{slash}US0_TX#0-Pad58)") (class "Default")
      (node (ref "IC2") (pin "58") (pinfunction "PE10/TIM1_CC0#1/US0_TX#0_58") (pintype "bidirectional"))
    )
    (net (code "74") (name "unconnected-(IC2E-PE11{slash}TIM1_CC1#1{slash}US0_RX#0-Pad59)") (class "Default")
      (node (ref "IC2") (pin "59") (pinfunction "PE11/TIM1_CC1#1/US0_RX#0_59") (pintype "bidirectional"))
    )
    (net (code "75") (name "unconnected-(IC2E-PE12{slash}TIM1_CC2#1{slash}US0_CLK#0-Pad60)") (class "Default")
      (node (ref "IC2") (pin "60") (pinfunction "PE12/TIM1_CC2#1/US0_CLK#0_60") (pintype "bidirectional"))
    )
    (net (code "76") (name "unconnected-(IC2E-PE13{slash}ACMP0_O{slash}US0_CS#0-Pad61)") (class "Default")
      (node (ref "IC2") (pin "61") (pinfunction "PE13/ACMP0_O/US0_CS#0_61") (pintype "bidirectional"))
    )
    (net (code "77") (name "unconnected-(IC2E-PE14{slash}LEU0_TX#2-Pad62)") (class "Default")
      (node (ref "IC2") (pin "62") (pinfunction "PE14/LEU0_TX#2_62") (pintype "bidirectional"))
    )
    (net (code "78") (name "unconnected-(IC2E-PE15{slash}LEU0_RX#2-Pad63)") (class "Default")
      (node (ref "IC2") (pin "63") (pinfunction "PE15/LEU0_RX#2_63") (pintype "bidirectional"))
    )
    (net (code "79") (name "unconnected-(IC2F-PF3{slash}TIM0_CDTI0#2-Pad52)") (class "Default")
      (node (ref "IC2") (pin "52") (pinfunction "PF3/TIM0_CDTI0#2_52") (pintype "bidirectional"))
    )
    (net (code "80") (name "unconnected-(IC2F-PF4{slash}TIM0_CDTI1#2-Pad53)") (class "Default")
      (node (ref "IC2") (pin "53") (pinfunction "PF4/TIM0_CDTI1#2_53") (pintype "bidirectional"))
    )
    (net (code "81") (name "unconnected-(IC2F-PF5{slash}TIM0_CDTI2#2-Pad54)") (class "Default")
      (node (ref "IC2") (pin "54") (pinfunction "PF5/TIM0_CDTI2#2_54") (pintype "bidirectional"))
    )
    (net (code "82") (name "unconnected-(IC3-PWGD-Pad6)") (class "Default")
      (node (ref "IC3") (pin "6") (pinfunction "PWGD_6") (pintype "output"))
    )
    (net (code "83") (name "unconnected-(X2-Pad7)") (class "Default")
      (node (ref "X2") (pin "7") (pinfunction "7_7") (pintype "passive"))
    )
  )
)
